# Main.net
KiCad netlist of a schematic drawn in Altium Designer
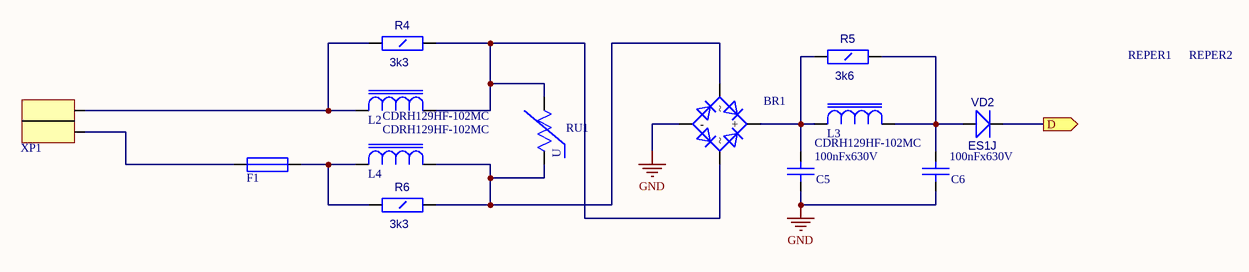
[diagram p0: Main.SchDoc]

(export (version "E")
  (design (tool "Eeschema 10.0.6"))
  (components
    (comp (ref "BR1") (value "DF10S") (footprint "SDIP") (libsource (lib "gprs_modem_2") (part "DF10S")))
    (comp (ref "C5")
      (value "100nFx630V")
      (footprint "CAP_630V_SMD")
      (libsource (lib "gprs_modem_2") (part "Cap_HV"))
    )
    (comp (ref "C6")
      (value "100nFx630V")
      (footprint "CAP_630V_SMD")
      (libsource (lib "gprs_modem_2") (part "Cap_HV"))
    )
    (comp (ref "F1")
      (value "*")
      (footprint "Fuse Belfuse")
      (libsource (lib "gprs_modem_2") (part "Fuse Belufse"))
    )
    (comp (ref "L2")
      (value "CDRH129HF-102MC")
      (footprint "IND_CDRH129")
      (libsource (lib "gprs_modem_2") (part "CDRH129"))
    )
    (comp (ref "L3")
      (value "CDRH129HF-102MC")
      (footprint "IND_CDRH129")
      (libsource (lib "gprs_modem_2") (part "CDRH129"))
    )
    (comp (ref "L4")
      (value "CDRH129HF-102MC")
      (footprint "IND_CDRH129")
      (libsource (lib "gprs_modem_2") (part "CDRH129"))
    )
    (comp (ref "R4")
      (value "3k3")
      (footprint "RC1206")
      (description "RC1206")
      (libsource (lib "gprs_modem_2") (part "RC1206"))
    )
    (comp (ref "R5")
      (value "3k6")
      (footprint "RC1206")
      (description "RC1206")
      (libsource (lib "gprs_modem_2") (part "RC1206"))
    )
    (comp (ref "R6")
      (value "3k3")
      (footprint "RC1206")
      (description "RC1206")
      (libsource (lib "gprs_modem_2") (part "RC1206"))
    )
    (comp (ref "REPER1")
      (value "REPER1.2")
      (footprint "REPER1.2")
      (libsource (lib "gprs_modem") (part "REPER1.2"))
    )
    (comp (ref "REPER2")
      (value "REPER1.2")
      (footprint "REPER1.2")
      (libsource (lib "gprs_modem") (part "REPER1.2"))
    )
    (comp (ref "RU1")
      (value "KLS6-07D")
      (footprint "Varistor_7mm_SMD")
      (libsource (lib "gprs_modem_2") (part "KLS6-07D"))
    )
    (comp (ref "VD2")
      (value "ES1J")
      (footprint "SMA")
      (description "Schottky Rectifier")
      (libsource (lib "gprs_modem_2") (part "SS14"))
    )
    (comp (ref "XP1")
      (value "*")
      (footprint "Poke-In 2pin")
      (libsource (lib "gprs_modem_2") (part "Poke-IN 2Pin"))
    )
  )
  (nets
    (net (code "1") (name "/D") (class "Default")
      (node (ref "VD2") (pin "2") (pinfunction "K_2") (pintype "passive"))
    )
    (net (code "2") (name "GND") (class "Default")
      (node (ref "BR1") (pin "2") (pinfunction "-_2") (pintype "passive"))
      (node (ref "C5") (pin "1") (pinfunction "A_1") (pintype "passive"))
      (node (ref "C6") (pin "1") (pinfunction "A_1") (pintype "passive"))
    )
    (net (code "3") (name "Net-(BR1-+)") (class "Default")
      (node (ref "BR1") (pin "1") (pinfunction "+_1") (pintype "passive"))
      (node (ref "C5") (pin "2") (pinfunction "B_2") (pintype "passive"))
      (node (ref "L3") (pin "1") (pinfunction "A_1") (pintype "passive"))
      (node (ref "R5") (pin "1") (pinfunction "A_1") (pintype "passive"))
    )
    (net (code "4") (name "Net-(C6-B)") (class "Default")
      (node (ref "C6") (pin "2") (pinfunction "B_2") (pintype "passive"))
      (node (ref "L3") (pin "2") (pinfunction "B_2") (pintype "passive"))
      (node (ref "R5") (pin "2") (pinfunction "B_2") (pintype "passive"))
      (node (ref "VD2") (pin "1") (pinfunction "A_1") (pintype "passive"))
    )
    (net (code "5") (name "Net-(L2-A)") (class "Default")
      (node (ref "L2") (pin "1") (pinfunction "A_1") (pintype "passive"))
      (node (ref "R4") (pin "1") (pinfunction "A_1") (pintype "passive"))
      (node (ref "XP1") (pin "3") (pinfunction "9_3") (pintype "passive"))
    )
    (net (code "6") (name "Net-(L2-B)") (class "Default")
      (node (ref "BR1") (pin "4") (pinfunction "~_4") (pintype "passive"))
      (node (ref "L2") (pin "2") (pinfunction "B_2") (pintype "passive"))
      (node (ref "R4") (pin "2") (pinfunction "B_2") (pintype "passive"))
      (node (ref "RU1") (pin "2") (pinfunction "B_2") (pintype "passive"))
    )
    (net (code "7") (name "Net-(L4-A)") (class "Default")
      (node (ref "F1") (pin "2") (pintype "passive"))
      (node (ref "L4") (pin "1") (pinfunction "A_1") (pintype "passive"))
      (node (ref "R6") (pin "1") (pinfunction "A_1") (pintype "passive"))
    )
    (net (code "8") (name "Net-(L4-B)") (class "Default")
      (node (ref "BR1") (pin "3") (pinfunction "~_3") (pintype "passive"))
      (node (ref "L4") (pin "2") (pinfunction "B_2") (pintype "passive"))
      (node (ref "R6") (pin "2") (pinfunction "B_2") (pintype "passive"))
      (node (ref "RU1") (pin "1") (pinfunction "A_1") (pintype "passive"))
    )
    (net (code "9") (name "Net-(XP1-10)") (class "Default")
      (node (ref "F1") (pin "1") (pintype "passive"))
      (node (ref "XP1") (pin "4") (pinfunction "10_4") (pintype "passive"))
    )
    (net (code "10") (name "unconnected-(REPER1-Pad1)") (class "Default")
      (node (ref "REPER1") (pin "1") (pintype "passive"))
    )
    (net (code "11") (name "unconnected-(REPER2-Pad1)") (class "Default")
      (node (ref "REPER2") (pin "1") (pintype "passive"))
    )
  )
)
